# motor_sch.net
KiCad netlist of a schematic drawn in Altium Designer
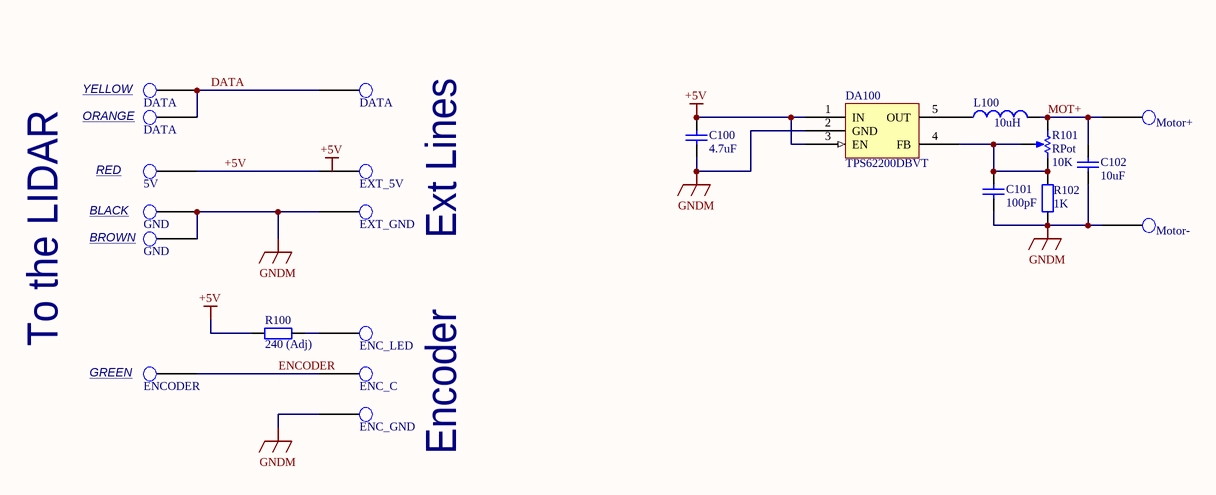
[diagram p0: motor_sch.SchDoc]

(export (version "E")
  (design (tool "Eeschema 10.0.6"))
  (components
    (comp (ref "C100")
      (value "4.7uF")
      (footprint "CAPC2012X135N")
      (description "Chip capacitor")
      (fields (field (name "VOLTAGE") "25V"))
      (libsource (lib "MyLibSch") (part "CC0805"))
    )
    (comp (ref "C101")
      (value "100pF")
      (footprint "CAPC1608X90N")
      (description "Chip capacitor")
      (fields (field (name "VOLTAGE") "25V"))
      (libsource (lib "MyLibSch") (part "CC0805"))
    )
    (comp (ref "C102")
      (value "10uF")
      (footprint "CAPC3216X100N")
      (description "Chip capacitor")
      (fields (field (name "VOLTAGE") "25V"))
      (libsource (lib "MyLibSch") (part "CC0805"))
    )
    (comp (ref "DA100")
      (value "TPS62200DBVT")
      (footprint "SOT23-5")
      (description "DC-DC step-down")
      (libsource (lib "lcd_lib") (part "TPS62200"))
    )
    (comp (ref "L100")
      (value "10uH")
      (footprint "INDC3216")
      (description "Inductor")
      (fields (field (name "PUBLISHER") "Altium Limited"))
      (libsource (lib "Miscellaneous Devices") (part "Inductor"))
    )
    (comp (ref "P101")
      (value "DATA")
      (footprint "Ext_pad")
      (description "Pad for wire")
      (libsource (lib "lcd_lib") (part "Ext Pad"))
    )
    (comp (ref "P102")
      (value "DATA")
      (footprint "Ext_pad")
      (description "Pad for wire")
      (libsource (lib "lcd_lib") (part "Ext Pad"))
    )
    (comp (ref "P103")
      (value "DATA")
      (footprint "Ext_pad")
      (description "Pad for wire")
      (libsource (lib "lcd_lib") (part "Ext Pad"))
    )
    (comp (ref "P104")
      (value "ENC_LED")
      (footprint "Ext_pad")
      (description "Pad for wire")
      (libsource (lib "lcd_lib") (part "Ext Pad"))
    )
    (comp (ref "P105")
      (value "ENC_C")
      (footprint "Ext_pad")
      (description "Pad for wire")
      (libsource (lib "lcd_lib") (part "Ext Pad"))
    )
    (comp (ref "P106")
      (value "ENC_GND")
      (footprint "Ext_pad")
      (description "Pad for wire")
      (libsource (lib "lcd_lib") (part "Ext Pad"))
    )
    (comp (ref "P107")
      (value "ENCODER")
      (footprint "Ext_pad")
      (description "Pad for wire")
      (libsource (lib "lcd_lib") (part "Ext Pad"))
    )
    (comp (ref "P109")
      (value "5V")
      (footprint "Ext_pad")
      (description "Pad for wire")
      (libsource (lib "lcd_lib") (part "Ext Pad"))
    )
    (comp (ref "P110")
      (value "EXT_5V")
      (footprint "Ext_pad")
      (description "Pad for wire")
      (libsource (lib "lcd_lib") (part "Ext Pad"))
    )
    (comp (ref "P111")
      (value "EXT_GND")
      (footprint "Ext_pad")
      (description "Pad for wire")
      (libsource (lib "lcd_lib") (part "Ext Pad"))
    )
    (comp (ref "P112")
      (value "Motor+")
      (footprint "PcbLib3:Ext_hole")
      (description "Hole Pad")
      (libsource (lib "lcd_lib") (part "Hole Pad"))
    )
    (comp (ref "P113")
      (value "Motor-")
      (footprint "PcbLib3:Ext_hole")
      (description "Hole Pad")
      (libsource (lib "lcd_lib") (part "Hole Pad"))
    )
    (comp (ref "P114")
      (value "GND")
      (footprint "Ext_pad")
      (description "Pad for wire")
      (libsource (lib "lcd_lib") (part "Ext Pad"))
    )
    (comp (ref "P115")
      (value "GND")
      (footprint "Ext_pad")
      (description "Pad for wire")
      (libsource (lib "lcd_lib") (part "Ext Pad"))
    )
    (comp (ref "R100")
      (value "240 (Adj)")
      (footprint "RESC1608X55N")
      (description "Chip resistor")
      (fields (field (name "TOLERANCE") "5%"))
      (libsource (lib "") (part "RC0805_1"))
    )
    (comp (ref "R101")
      (value "RPot")
      (footprint "VR5")
      (description "Potentiometer")
      (fields (field (name "ALTIUM_VALUE") "10K") (field (name "PUBLISHER") "Altium Limited"))
      (libsource (lib "Miscellaneous Devices") (part "RPot"))
    )
    (comp (ref "R102")
      (value "1K")
      (footprint "RESC1608X55N")
      (description "Chip resistor")
      (fields (field (name "TOLERANCE") "5%"))
      (libsource (lib "MyLibSch") (part "RC0805"))
    )
  )
  (nets
    (net (code "1") (name "+5V") (class "Default")
      (node (ref "C100") (pin "2") (pinfunction "2_2") (pintype "passive"))
      (node (ref "DA100") (pin "1") (pinfunction "IN_1") (pintype "power_in"))
      (node (ref "DA100") (pin "3") (pinfunction "EN_3") (pintype "input"))
      (node (ref "P109") (pin "1") (pinfunction "Pad_1") (pintype "passive"))
      (node (ref "P110") (pin "1") (pinfunction "Pad_1") (pintype "passive"))
      (node (ref "R100") (pin "2") (pinfunction "2_2") (pintype "passive"))
    )
    (net (code "2") (name "/DATA") (class "Default")
      (node (ref "P101") (pin "1") (pinfunction "Pad_1") (pintype "passive"))
      (node (ref "P102") (pin "1") (pinfunction "Pad_1") (pintype "passive"))
      (node (ref "P103") (pin "1") (pinfunction "Pad_1") (pintype "passive"))
    )
    (net (code "3") (name "/ENCODER") (class "Default")
      (node (ref "P105") (pin "1") (pinfunction "Pad_1") (pintype "passive"))
      (node (ref "P107") (pin "1") (pinfunction "Pad_1") (pintype "passive"))
    )
    (net (code "4") (name "/MOT+") (class "Default")
      (node (ref "C102") (pin "2") (pinfunction "2_2") (pintype "passive"))
      (node (ref "L100") (pin "2") (pinfunction "2_2") (pintype "passive"))
      (node (ref "P112") (pin "1") (pinfunction "Pad_1") (pintype "passive"))
      (node (ref "R101") (pin "1") (pinfunction "TOP_1") (pintype "passive"))
    )
    (net (code "5") (name "GNDM") (class "Default")
      (node (ref "C100") (pin "1") (pinfunction "1_1") (pintype "passive"))
      (node (ref "C101") (pin "1") (pinfunction "1_1") (pintype "passive"))
      (node (ref "C102") (pin "1") (pinfunction "1_1") (pintype "passive"))
      (node (ref "DA100") (pin "2") (pinfunction "GND_2") (pintype "power_in"))
      (node (ref "P106") (pin "1") (pinfunction "Pad_1") (pintype "passive"))
      (node (ref "P111") (pin "1") (pinfunction "Pad_1") (pintype "passive"))
      (node (ref "P113") (pin "1") (pinfunction "Pad_1") (pintype "passive"))
      (node (ref "P114") (pin "1") (pinfunction "Pad_1") (pintype "passive"))
      (node (ref "P115") (pin "1") (pinfunction "Pad_1") (pintype "passive"))
      (node (ref "R102") (pin "1") (pinfunction "1_1") (pintype "passive"))
    )
    (net (code "6") (name "Net-(DA100-FB)") (class "Default")
      (node (ref "C101") (pin "2") (pinfunction "2_2") (pintype "passive"))
      (node (ref "DA100") (pin "4") (pinfunction "FB_4") (pintype "passive"))
      (node (ref "R101") (pin "2") (pinfunction "BOT_2") (pintype "passive"))
      (node (ref "R101") (pin "3") (pinfunction "TAP_3") (pintype "passive"))
      (node (ref "R102") (pin "2") (pinfunction "2_2") (pintype "passive"))
    )
    (net (code "7") (name "Net-(DA100-OUT)") (class "Default")
      (node (ref "DA100") (pin "5") (pinfunction "OUT_5") (pintype "passive"))
      (node (ref "L100") (pin "1") (pinfunction "1_1") (pintype "passive"))
    )
    (net (code "8") (name "Net-(P104-Pad)") (class "Default")
      (node (ref "P104") (pin "1") (pinfunction "Pad_1") (pintype "passive"))
      (node (ref "R100") (pin "1") (pinfunction "1_1") (pintype "passive"))
    )
  )
)
